# roboproj_q2.net
KiCad netlist of a schematic drawn in EAGLE
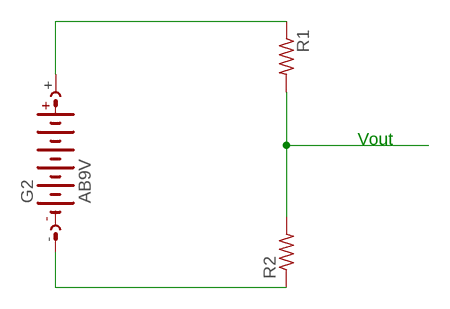
[diagram p0: schematic, sheet 1]

(export (version "E")
  (design (tool "Eeschema 10.0.6"))
  (components
    (comp (ref "G2")
      (value "AB9V")
      (footprint "eagle-import:AB9V")
      (libsource (lib "eagle-import") (part "AB9V"))
    )
    (comp (ref "R1")
      (value "R-US_R0805")
      (footprint "eagle-import:R0805")
      (libsource (lib "eagle-import") (part "R-US_R0805"))
    )
    (comp (ref "R2")
      (value "R-US_R0805")
      (footprint "eagle-import:R0805")
      (libsource (lib "eagle-import") (part "R-US_R0805"))
    )
  )
  (nets
    (net (code "1") (name "Net-(G2-Pad+)") (class "Default")
      (node (ref "G2") (pin "+") (pinfunction "+_+") (pintype "passive"))
      (node (ref "R1") (pin "1") (pinfunction "1_1") (pintype "passive"))
    )
    (net (code "2") (name "Net-(G2-Pad-)") (class "Default")
      (node (ref "G2") (pin "-") (pinfunction "-_-") (pintype "passive"))
      (node (ref "R2") (pin "1") (pinfunction "1_1") (pintype "passive"))
    )
    (net (code "3") (name "Net-(R1-Pad2)") (class "Default")
      (node (ref "R1") (pin "2") (pinfunction "2_2") (pintype "passive"))
      (node (ref "R2") (pin "2") (pinfunction "2_2") (pintype "passive"))
    )
  )
)
